# Input_v1_0.net
KiCad netlist of a schematic drawn in EAGLE
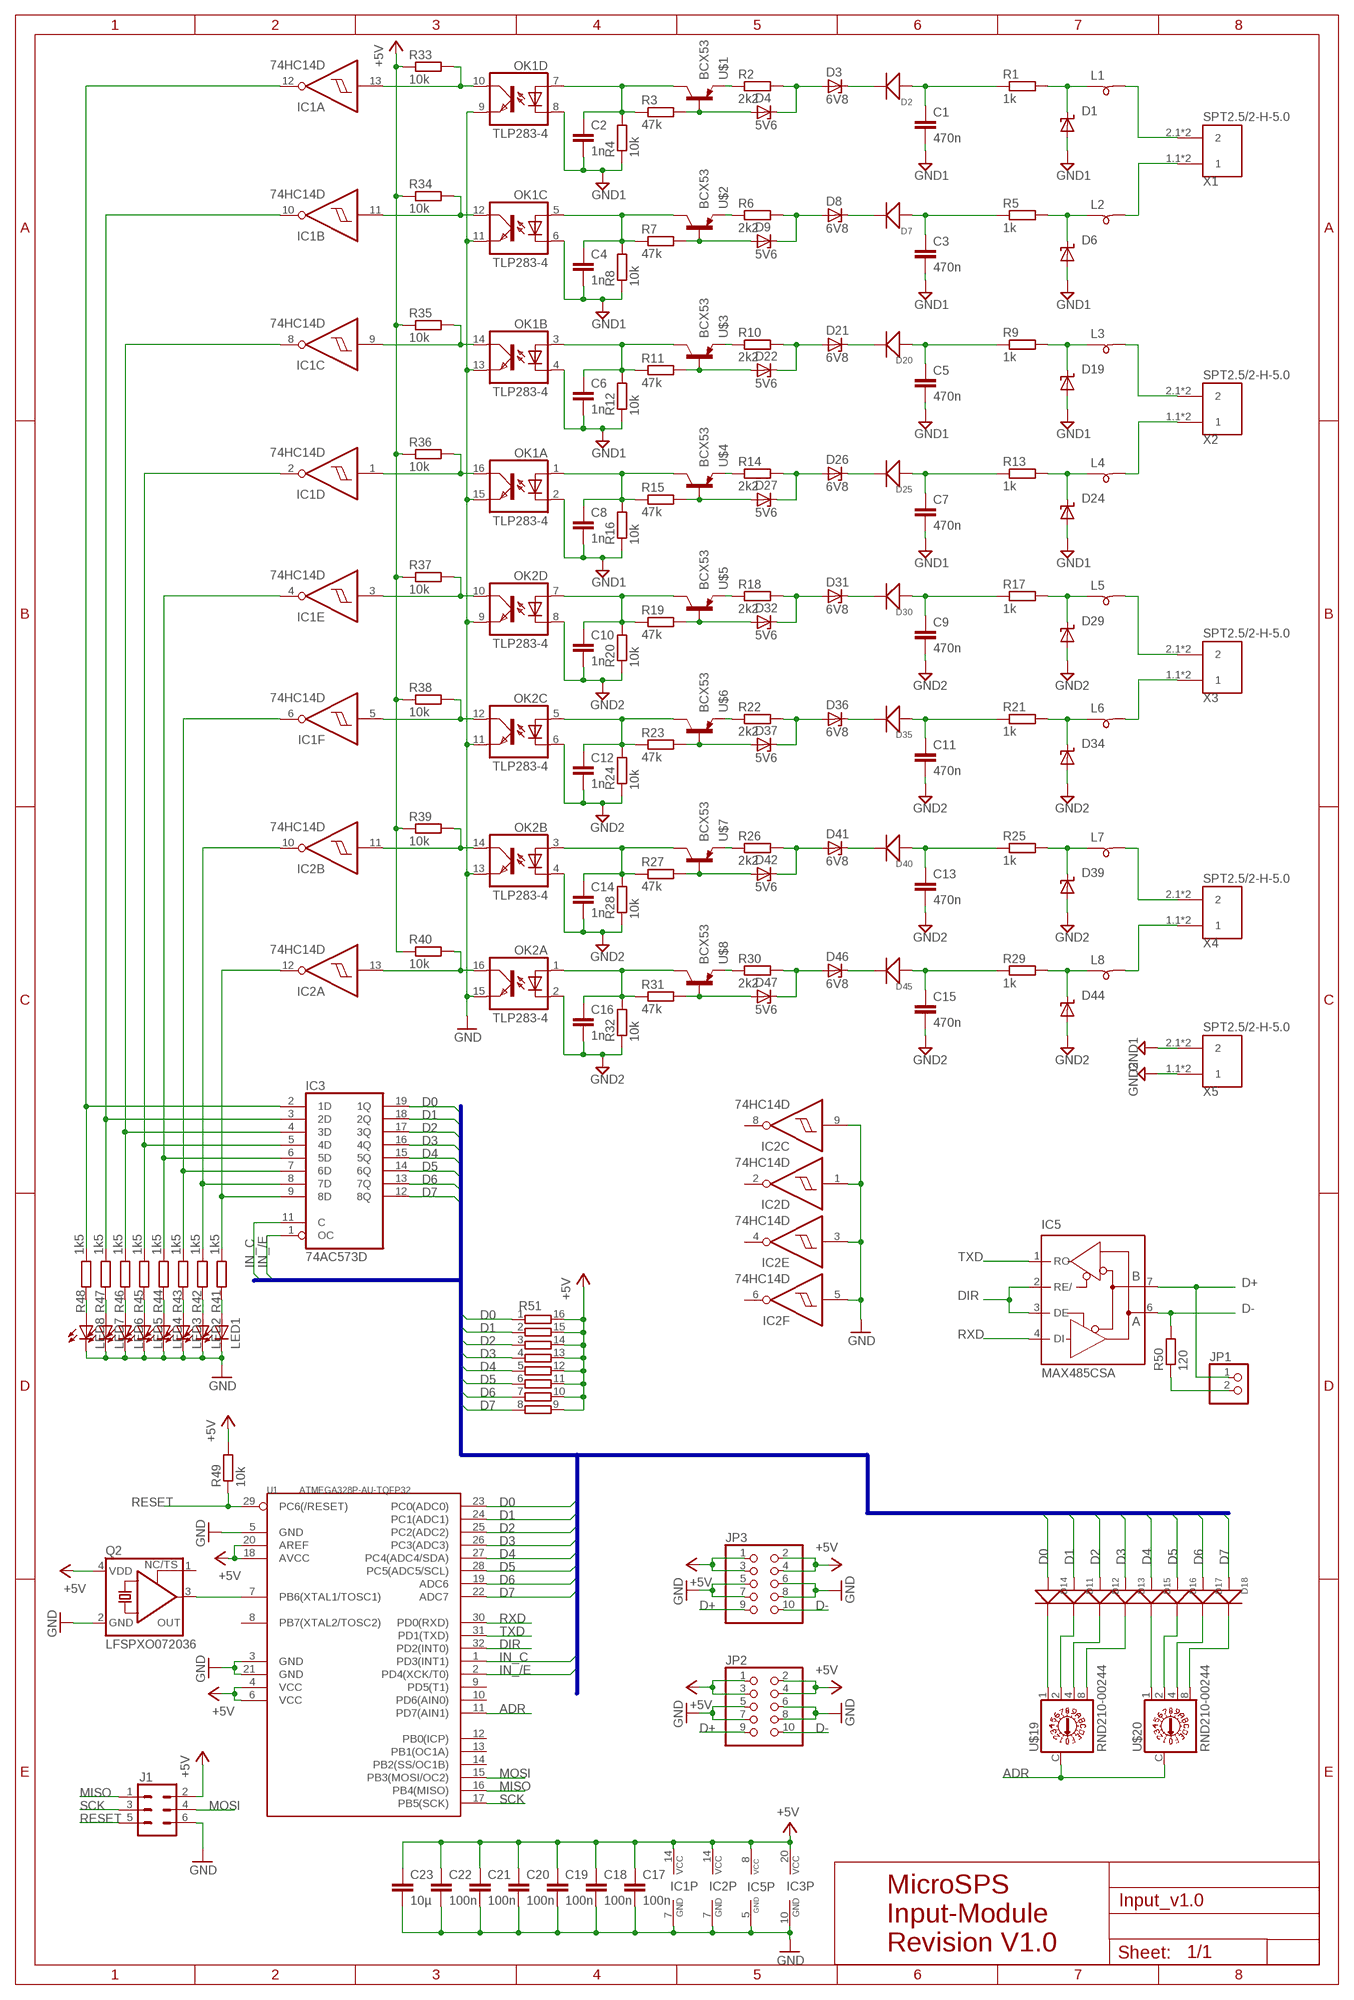
[diagram p0: schematic, sheet 1]

(export (version "E")
  (design (tool "Eeschema 10.0.6"))
  (components
    (comp (ref "C1")
      (value "470n")
      (footprint "eagle-import:C0805")
      (libsource (lib "eagle-import") (part "C-EUC0805"))
    )
    (comp (ref "C2")
      (value "1n")
      (footprint "eagle-import:C0805")
      (libsource (lib "eagle-import") (part "C-EUC0805"))
    )
    (comp (ref "C3")
      (value "470n")
      (footprint "eagle-import:C0805")
      (libsource (lib "eagle-import") (part "C-EUC0805"))
    )
    (comp (ref "C4")
      (value "1n")
      (footprint "eagle-import:C0805")
      (libsource (lib "eagle-import") (part "C-EUC0805"))
    )
    (comp (ref "C5")
      (value "470n")
      (footprint "eagle-import:C0805")
      (libsource (lib "eagle-import") (part "C-EUC0805"))
    )
    (comp (ref "C6")
      (value "1n")
      (footprint "eagle-import:C0805")
      (libsource (lib "eagle-import") (part "C-EUC0805"))
    )
    (comp (ref "C7")
      (value "470n")
      (footprint "eagle-import:C0805")
      (libsource (lib "eagle-import") (part "C-EUC0805"))
    )
    (comp (ref "C8")
      (value "1n")
      (footprint "eagle-import:C0805")
      (libsource (lib "eagle-import") (part "C-EUC0805"))
    )
    (comp (ref "C9")
      (value "470n")
      (footprint "eagle-import:C0805")
      (libsource (lib "eagle-import") (part "C-EUC0805"))
    )
    (comp (ref "C10")
      (value "1n")
      (footprint "eagle-import:C0805")
      (libsource (lib "eagle-import") (part "C-EUC0805"))
    )
    (comp (ref "C11")
      (value "470n")
      (footprint "eagle-import:C0805")
      (libsource (lib "eagle-import") (part "C-EUC0805"))
    )
    (comp (ref "C12")
      (value "1n")
      (footprint "eagle-import:C0805")
      (libsource (lib "eagle-import") (part "C-EUC0805"))
    )
    (comp (ref "C13")
      (value "470n")
      (footprint "eagle-import:C0805")
      (libsource (lib "eagle-import") (part "C-EUC0805"))
    )
    (comp (ref "C14")
      (value "1n")
      (footprint "eagle-import:C0805")
      (libsource (lib "eagle-import") (part "C-EUC0805"))
    )
    (comp (ref "C15")
      (value "470n")
      (footprint "eagle-import:C0805")
      (libsource (lib "eagle-import") (part "C-EUC0805"))
    )
    (comp (ref "C16")
      (value "1n")
      (footprint "eagle-import:C0805")
      (libsource (lib "eagle-import") (part "C-EUC0805"))
    )
    (comp (ref "C17")
      (value "100n")
      (footprint "eagle-import:C0805")
      (libsource (lib "eagle-import") (part "C-EUC0805"))
    )
    (comp (ref "C18")
      (value "100n")
      (footprint "eagle-import:C0805")
      (libsource (lib "eagle-import") (part "C-EUC0805"))
    )
    (comp (ref "C19")
      (value "100n")
      (footprint "eagle-import:C0805")
      (libsource (lib "eagle-import") (part "C-EUC0805"))
    )
    (comp (ref "C20")
      (value "100n")
      (footprint "eagle-import:C0805")
      (libsource (lib "eagle-import") (part "C-EUC0805"))
    )
    (comp (ref "C21")
      (value "100n")
      (footprint "eagle-import:C0805")
      (libsource (lib "eagle-import") (part "C-EUC0805"))
    )
    (comp (ref "C22")
      (value "100n")
      (footprint "eagle-import:C0805")
      (libsource (lib "eagle-import") (part "C-EUC0805"))
    )
    (comp (ref "C23")
      (value "10µ")
      (footprint "eagle-import:C0805")
      (libsource (lib "eagle-import") (part "C-EUC0805"))
    )
    (comp (ref "D1")
      (value "SUPPRESSOR-SMBJ")
      (footprint "eagle-import:SMBJ")
      (libsource (lib "eagle-import") (part "SUPPRESSOR-SMBJ"))
    )
    (comp (ref "D2")
      (value "DIODE'1N4148-SMD'")
      (footprint "eagle-import:LL-34")
      (libsource (lib "eagle-import") (part "DIODE'1N4148-SMD'"))
    )
    (comp (ref "D3")
      (value "6V8")
      (footprint "eagle-import:SOD80C")
      (libsource (lib "eagle-import") (part "ZENER-DIODESOD80C"))
    )
    (comp (ref "D4")
      (value "5V6")
      (footprint "eagle-import:SOD80C")
      (libsource (lib "eagle-import") (part "ZENER-DIODESOD80C"))
    )
    (comp (ref "D6")
      (value "SUPPRESSOR-SMBJ")
      (footprint "eagle-import:SMBJ")
      (libsource (lib "eagle-import") (part "SUPPRESSOR-SMBJ"))
    )
    (comp (ref "D7")
      (value "DIODE'1N4148-SMD'")
      (footprint "eagle-import:LL-34")
      (libsource (lib "eagle-import") (part "DIODE'1N4148-SMD'"))
    )
    (comp (ref "D8")
      (value "6V8")
      (footprint "eagle-import:SOD80C")
      (libsource (lib "eagle-import") (part "ZENER-DIODESOD80C"))
    )
    (comp (ref "D9")
      (value "5V6")
      (footprint "eagle-import:SOD80C")
      (libsource (lib "eagle-import") (part "ZENER-DIODESOD80C"))
    )
    (comp (ref "D11")
      (value "DIODE'1N4148-SMD'")
      (footprint "eagle-import:LL-34")
      (libsource (lib "eagle-import") (part "DIODE'1N4148-SMD'"))
    )
    (comp (ref "D12")
      (value "DIODE'1N4148-SMD'")
      (footprint "eagle-import:LL-34")
      (libsource (lib "eagle-import") (part "DIODE'1N4148-SMD'"))
    )
    (comp (ref "D13")
      (value "DIODE'1N4148-SMD'")
      (footprint "eagle-import:LL-34")
      (libsource (lib "eagle-import") (part "DIODE'1N4148-SMD'"))
    )
    (comp (ref "D14")
      (value "DIODE'1N4148-SMD'")
      (footprint "eagle-import:LL-34")
      (libsource (lib "eagle-import") (part "DIODE'1N4148-SMD'"))
    )
    (comp (ref "D15")
      (value "DIODE'1N4148-SMD'")
      (footprint "eagle-import:LL-34")
      (libsource (lib "eagle-import") (part "DIODE'1N4148-SMD'"))
    )
    (comp (ref "D16")
      (value "DIODE'1N4148-SMD'")
      (footprint "eagle-import:LL-34")
      (libsource (lib "eagle-import") (part "DIODE'1N4148-SMD'"))
    )
    (comp (ref "D17")
      (value "DIODE'1N4148-SMD'")
      (footprint "eagle-import:LL-34")
      (libsource (lib "eagle-import") (part "DIODE'1N4148-SMD'"))
    )
    (comp (ref "D18")
      (value "DIODE'1N4148-SMD'")
      (footprint "eagle-import:LL-34")
      (libsource (lib "eagle-import") (part "DIODE'1N4148-SMD'"))
    )
    (comp (ref "D19")
      (value "SUPPRESSOR-SMBJ")
      (footprint "eagle-import:SMBJ")
      (libsource (lib "eagle-import") (part "SUPPRESSOR-SMBJ"))
    )
    (comp (ref "D20")
      (value "DIODE'1N4148-SMD'")
      (footprint "eagle-import:LL-34")
      (libsource (lib "eagle-import") (part "DIODE'1N4148-SMD'"))
    )
    (comp (ref "D21")
      (value "6V8")
      (footprint "eagle-import:SOD80C")
      (libsource (lib "eagle-import") (part "ZENER-DIODESOD80C"))
    )
    (comp (ref "D22")
      (value "5V6")
      (footprint "eagle-import:SOD80C")
      (libsource (lib "eagle-import") (part "ZENER-DIODESOD80C"))
    )
    (comp (ref "D24")
      (value "SUPPRESSOR-SMBJ")
      (footprint "eagle-import:SMBJ")
      (libsource (lib "eagle-import") (part "SUPPRESSOR-SMBJ"))
    )
    (comp (ref "D25")
      (value "DIODE'1N4148-SMD'")
      (footprint "eagle-import:LL-34")
      (libsource (lib "eagle-import") (part "DIODE'1N4148-SMD'"))
    )
    (comp (ref "D26")
      (value "6V8")
      (footprint "eagle-import:SOD80C")
      (libsource (lib "eagle-import") (part "ZENER-DIODESOD80C"))
    )
    (comp (ref "D27")
      (value "5V6")
      (footprint "eagle-import:SOD80C")
      (libsource (lib "eagle-import") (part "ZENER-DIODESOD80C"))
    )
    (comp (ref "D29")
      (value "SUPPRESSOR-SMBJ")
      (footprint "eagle-import:SMBJ")
      (libsource (lib "eagle-import") (part "SUPPRESSOR-SMBJ"))
    )
    (comp (ref "D30")
      (value "DIODE'1N4148-SMD'")
      (footprint "eagle-import:LL-34")
      (libsource (lib "eagle-import") (part "DIODE'1N4148-SMD'"))
    )
    (comp (ref "D31")
      (value "6V8")
      (footprint "eagle-import:SOD80C")
      (libsource (lib "eagle-import") (part "ZENER-DIODESOD80C"))
    )
    (comp (ref "D32")
      (value "5V6")
      (footprint "eagle-import:SOD80C")
      (libsource (lib "eagle-import") (part "ZENER-DIODESOD80C"))
    )
    (comp (ref "D34")
      (value "SUPPRESSOR-SMBJ")
      (footprint "eagle-import:SMBJ")
      (libsource (lib "eagle-import") (part "SUPPRESSOR-SMBJ"))
    )
    (comp (ref "D35")
      (value "DIODE'1N4148-SMD'")
      (footprint "eagle-import:LL-34")
      (libsource (lib "eagle-import") (part "DIODE'1N4148-SMD'"))
    )
    (comp (ref "D36")
      (value "6V8")
      (footprint "eagle-import:SOD80C")
      (libsource (lib "eagle-import") (part "ZENER-DIODESOD80C"))
    )
    (comp (ref "D37")
      (value "5V6")
      (footprint "eagle-import:SOD80C")
      (libsource (lib "eagle-import") (part "ZENER-DIODESOD80C"))
    )
    (comp (ref "D39")
      (value "SUPPRESSOR-SMBJ")
      (footprint "eagle-import:SMBJ")
      (libsource (lib "eagle-import") (part "SUPPRESSOR-SMBJ"))
    )
    (comp (ref "D40")
      (value "DIODE'1N4148-SMD'")
      (footprint "eagle-import:LL-34")
      (libsource (lib "eagle-import") (part "DIODE'1N4148-SMD'"))
    )
    (comp (ref "D41")
      (value "6V8")
      (footprint "eagle-import:SOD80C")
      (libsource (lib "eagle-import") (part "ZENER-DIODESOD80C"))
    )
    (comp (ref "D42")
      (value "5V6")
      (footprint "eagle-import:SOD80C")
      (libsource (lib "eagle-import") (part "ZENER-DIODESOD80C"))
    )
    (comp (ref "D44")
      (value "SUPPRESSOR-SMBJ")
      (footprint "eagle-import:SMBJ")
      (libsource (lib "eagle-import") (part "SUPPRESSOR-SMBJ"))
    )
    (comp (ref "D45")
      (value "DIODE'1N4148-SMD'")
      (footprint "eagle-import:LL-34")
      (libsource (lib "eagle-import") (part "DIODE'1N4148-SMD'"))
    )
    (comp (ref "D46")
      (value "6V8")
      (footprint "eagle-import:SOD80C")
      (libsource (lib "eagle-import") (part "ZENER-DIODESOD80C"))
    )
    (comp (ref "D47")
      (value "5V6")
      (footprint "eagle-import:SOD80C")
      (libsource (lib "eagle-import") (part "ZENER-DIODESOD80C"))
    )
    (comp (ref "IC1")
      (value "74HC14D")
      (footprint "eagle-import:SO14")
      (libsource (lib "eagle-import") (part "7414DHC"))
    )
    (comp (ref "IC2")
      (value "74HC14D")
      (footprint "eagle-import:SO14")
      (libsource (lib "eagle-import") (part "7414DHC"))
    )
    (comp (ref "IC3")
      (value "74AC573D")
      (footprint "eagle-import:SO20W")
      (libsource (lib "eagle-import") (part "74573DAC"))
    )
    (comp (ref "IC5")
      (value "MAX485CSA")
      (footprint "eagle-import:SO08")
      (fields (field (name "MF") "MAXIM") (field (name "MPN") "MAX481CSA"))
      (libsource (lib "eagle-import") (part "MAX481CSA"))
    )
    (comp (ref "J1")
      (value "CONN_03X2FEMALE_SMD")
      (footprint "eagle-import:2X3_SMD")
      (libsource (lib "eagle-import") (part "CONN_03X2FEMALE_SMD"))
    )
    (comp (ref "JP1")
      (value "PINHD-1X2")
      (footprint "eagle-import:1X02")
      (libsource (lib "eagle-import") (part "PINHD-1X2"))
    )
    (comp (ref "JP2")
      (value "PINHD-2X5/90")
      (footprint "eagle-import:2X05_90")
      (libsource (lib "eagle-import") (part "PINHD-2X5/90"))
    )
    (comp (ref "JP3")
      (value "PINHD-2X5/90")
      (footprint "eagle-import:2X05_90")
      (libsource (lib "eagle-import") (part "PINHD-2X5/90"))
    )
    (comp (ref "L1")
      (value "SM-B5")
      (footprint "eagle-import:SM-B5")
      (libsource (lib "eagle-import") (part "SM-B5"))
    )
    (comp (ref "L2")
      (value "SM-B5")
      (footprint "eagle-import:SM-B5")
      (libsource (lib "eagle-import") (part "SM-B5"))
    )
    (comp (ref "L3")
      (value "SM-B5")
      (footprint "eagle-import:SM-B5")
      (libsource (lib "eagle-import") (part "SM-B5"))
    )
    (comp (ref "L4")
      (value "SM-B5")
      (footprint "eagle-import:SM-B5")
      (libsource (lib "eagle-import") (part "SM-B5"))
    )
    (comp (ref "L5")
      (value "SM-B5")
      (footprint "eagle-import:SM-B5")
      (libsource (lib "eagle-import") (part "SM-B5"))
    )
    (comp (ref "L6")
      (value "SM-B5")
      (footprint "eagle-import:SM-B5")
      (libsource (lib "eagle-import") (part "SM-B5"))
    )
    (comp (ref "L7")
      (value "SM-B5")
      (footprint "eagle-import:SM-B5")
      (libsource (lib "eagle-import") (part "SM-B5"))
    )
    (comp (ref "L8")
      (value "SM-B5")
      (footprint "eagle-import:SM-B5")
      (libsource (lib "eagle-import") (part "SM-B5"))
    )
    (comp (ref "LED1")
      (value "LED3MM")
      (footprint "eagle-import:LED3MM")
      (libsource (lib "eagle-import") (part "LED3MM"))
    )
    (comp (ref "LED2")
      (value "LED3MM")
      (footprint "eagle-import:LED3MM")
      (libsource (lib "eagle-import") (part "LED3MM"))
    )
    (comp (ref "LED3")
      (value "LED3MM")
      (footprint "eagle-import:LED3MM")
      (libsource (lib "eagle-import") (part "LED3MM"))
    )
    (comp (ref "LED4")
      (value "LED3MM")
      (footprint "eagle-import:LED3MM")
      (libsource (lib "eagle-import") (part "LED3MM"))
    )
    (comp (ref "LED5")
      (value "LED3MM")
      (footprint "eagle-import:LED3MM")
      (libsource (lib "eagle-import") (part "LED3MM"))
    )
    (comp (ref "LED6")
      (value "LED3MM")
      (footprint "eagle-import:LED3MM")
      (libsource (lib "eagle-import") (part "LED3MM"))
    )
    (comp (ref "LED7")
      (value "LED3MM")
      (footprint "eagle-import:LED3MM")
      (libsource (lib "eagle-import") (part "LED3MM"))
    )
    (comp (ref "LED8")
      (value "LED3MM")
      (footprint "eagle-import:LED3MM")
      (libsource (lib "eagle-import") (part "LED3MM"))
    )
    (comp (ref "OK1")
      (value "TLP283-4")
      (footprint "eagle-import:MINI-FLAT-16")
      (libsource (lib "eagle-import") (part "TLP283-4"))
    )
    (comp (ref "OK2")
      (value "TLP283-4")
      (footprint "eagle-import:MINI-FLAT-16")
      (libsource (lib "eagle-import") (part "TLP283-4"))
    )
    (comp (ref "Q2")
      (value "LFSPXO072036")
      (footprint "eagle-import:5.0X3.2_KXO-56")
      (libsource (lib "eagle-import") (part "KXO-PXO/XO-56-56"))
    )
    (comp (ref "R1")
      (value "1k")
      (footprint "eagle-import:R0805")
      (libsource (lib "eagle-import") (part "R-EU_R0805"))
    )
    (comp (ref "R2")
      (value "2k2")
      (footprint "eagle-import:R0805")
      (libsource (lib "eagle-import") (part "R-EU_R0805"))
    )
    (comp (ref "R3")
      (value "47k")
      (footprint "eagle-import:R0805")
      (libsource (lib "eagle-import") (part "R-EU_R0805"))
    )
    (comp (ref "R4")
      (value "10k")
      (footprint "eagle-import:R0805")
      (libsource (lib "eagle-import") (part "R-EU_R0805"))
    )
    (comp (ref "R5")
      (value "1k")
      (footprint "eagle-import:R0805")
      (libsource (lib "eagle-import") (part "R-EU_R0805"))
    )
    (comp (ref "R6")
      (value "2k2")
      (footprint "eagle-import:R0805")
      (libsource (lib "eagle-import") (part "R-EU_R0805"))
    )
    (comp (ref "R7")
      (value "47k")
      (footprint "eagle-import:R0805")
      (libsource (lib "eagle-import") (part "R-EU_R0805"))
    )
    (comp (ref "R8")
      (value "10k")
      (footprint "eagle-import:R0805")
      (libsource (lib "eagle-import") (part "R-EU_R0805"))
    )
    (comp (ref "R9")
      (value "1k")
      (footprint "eagle-import:R0805")
      (libsource (lib "eagle-import") (part "R-EU_R0805"))
    )
    (comp (ref "R10")
      (value "2k2")
      (footprint "eagle-import:R0805")
      (libsource (lib "eagle-import") (part "R-EU_R0805"))
    )
    (comp (ref "R11")
      (value "47k")
      (footprint "eagle-import:R0805")
      (libsource (lib "eagle-import") (part "R-EU_R0805"))
    )
    (comp (ref "R12")
      (value "10k")
      (footprint "eagle-import:R0805")
      (libsource (lib "eagle-import") (part "R-EU_R0805"))
    )
    (comp (ref "R13")
      (value "1k")
      (footprint "eagle-import:R0805")
      (libsource (lib "eagle-import") (part "R-EU_R0805"))
    )
    (comp (ref "R14")
      (value "2k2")
      (footprint "eagle-import:R0805")
      (libsource (lib "eagle-import") (part "R-EU_R0805"))
    )
    (comp (ref "R15")
      (value "47k")
      (footprint "eagle-import:R0805")
      (libsource (lib "eagle-import") (part "R-EU_R0805"))
    )
    (comp (ref "R16")
      (value "10k")
      (footprint "eagle-import:R0805")
      (libsource (lib "eagle-import") (part "R-EU_R0805"))
    )
    (comp (ref "R17")
      (value "1k")
      (footprint "eagle-import:R0805")
      (libsource (lib "eagle-import") (part "R-EU_R0805"))
    )
    (comp (ref "R18")
      (value "2k2")
      (footprint "eagle-import:R0805")
      (libsource (lib "eagle-import") (part "R-EU_R0805"))
    )
    (comp (ref "R19")
      (value "47k")
      (footprint "eagle-import:R0805")
      (libsource (lib "eagle-import") (part "R-EU_R0805"))
    )
    (comp (ref "R20")
      (value "10k")
      (footprint "eagle-import:R0805")
      (libsource (lib "eagle-import") (part "R-EU_R0805"))
    )
    (comp (ref "R21")
      (value "1k")
      (footprint "eagle-import:R0805")
      (libsource (lib "eagle-import") (part "R-EU_R0805"))
    )
    (comp (ref "R22")
      (value "2k2")
      (footprint "eagle-import:R0805")
      (libsource (lib "eagle-import") (part "R-EU_R0805"))
    )
    (comp (ref "R23")
      (value "47k")
      (footprint "eagle-import:R0805")
      (libsource (lib "eagle-import") (part "R-EU_R0805"))
    )
    (comp (ref "R24")
      (value "10k")
      (footprint "eagle-import:R0805")
      (libsource (lib "eagle-import") (part "R-EU_R0805"))
    )
    (comp (ref "R25")
      (value "1k")
      (footprint "eagle-import:R0805")
      (libsource (lib "eagle-import") (part "R-EU_R0805"))
    )
    (comp (ref "R26")
      (value "2k2")
      (footprint "eagle-import:R0805")
      (libsource (lib "eagle-import") (part "R-EU_R0805"))
    )
    (comp (ref "R27")
      (value "47k")
      (footprint "eagle-import:R0805")
      (libsource (lib "eagle-import") (part "R-EU_R0805"))
    )
    (comp (ref "R28")
      (value "10k")
      (footprint "eagle-import:R0805")
      (libsource (lib "eagle-import") (part "R-EU_R0805"))
    )
    (comp (ref "R29")
      (value "1k")
      (footprint "eagle-import:R0805")
      (libsource (lib "eagle-import") (part "R-EU_R0805"))
    )
    (comp (ref "R30")
      (value "2k2")
      (footprint "eagle-import:R0805")
      (libsource (lib "eagle-import") (part "R-EU_R0805"))
    )
    (comp (ref "R31")
      (value "47k")
      (footprint "eagle-import:R0805")
      (libsource (lib "eagle-import") (part "R-EU_R0805"))
    )
    (comp (ref "R32")
      (value "10k")
      (footprint "eagle-import:R0805")
      (libsource (lib "eagle-import") (part "R-EU_R0805"))
    )
    (comp (ref "R33")
      (value "10k")
      (footprint "eagle-import:R0805")
      (libsource (lib "eagle-import") (part "R-EU_R0805"))
    )
    (comp (ref "R34")
      (value "10k")
      (footprint "eagle-import:R0805")
      (libsource (lib "eagle-import") (part "R-EU_R0805"))
    )
    (comp (ref "R35")
      (value "10k")
      (footprint "eagle-import:R0805")
      (libsource (lib "eagle-import") (part "R-EU_R0805"))
    )
    (comp (ref "R36")
      (value "10k")
      (footprint "eagle-import:R0805")
      (libsource (lib "eagle-import") (part "R-EU_R0805"))
    )
    (comp (ref "R37")
      (value "10k")
      (footprint "eagle-import:R0805")
      (libsource (lib "eagle-import") (part "R-EU_R0805"))
    )
    (comp (ref "R38")
      (value "10k")
      (footprint "eagle-import:R0805")
      (libsource (lib "eagle-import") (part "R-EU_R0805"))
    )
    (comp (ref "R39")
      (value "10k")
      (footprint "eagle-import:R0805")
      (libsource (lib "eagle-import") (part "R-EU_R0805"))
    )
    (comp (ref "R40")
      (value "10k")
      (footprint "eagle-import:R0805")
      (libsource (lib "eagle-import") (part "R-EU_R0805"))
    )
    (comp (ref "R41")
      (value "1k5")
      (footprint "eagle-import:R0805")
      (libsource (lib "eagle-import") (part "R-EU_R0805"))
    )
    (comp (ref "R42")
      (value "1k5")
      (footprint "eagle-import:R0805")
      (libsource (lib "eagle-import") (part "R-EU_R0805"))
    )
    (comp (ref "R43")
      (value "1k5")
      (footprint "eagle-import:R0805")
      (libsource (lib "eagle-import") (part "R-EU_R0805"))
    )
    (comp (ref "R44")
      (value "1k5")
      (footprint "eagle-import:R0805")
      (libsource (lib "eagle-import") (part "R-EU_R0805"))
    )
    (comp (ref "R45")
      (value "1k5")
      (footprint "eagle-import:R0805")
      (libsource (lib "eagle-import") (part "R-EU_R0805"))
    )
    (comp (ref "R46")
      (value "1k5")
      (footprint "eagle-import:R0805")
      (libsource (lib "eagle-import") (part "R-EU_R0805"))
    )
    (comp (ref "R47")
      (value "1k5")
      (footprint "eagle-import:R0805")
      (libsource (lib "eagle-import") (part "R-EU_R0805"))
    )
    (comp (ref "R48")
      (value "1k5")
      (footprint "eagle-import:R0805")
      (libsource (lib "eagle-import") (part "R-EU_R0805"))
    )
    (comp (ref "R49")
      (value "10k")
      (footprint "eagle-import:R0805")
      (libsource (lib "eagle-import") (part "R-EU_R0805"))
    )
    (comp (ref "R50")
      (value "120")
      (footprint "eagle-import:R0805")
      (libsource (lib "eagle-import") (part "R-EU_R0805"))
    )
    (comp (ref "R51")
      (value "4816P-T01")
      (footprint "eagle-import:4816P")
      (fields (field (name "MF") "BOURNS, INC.") (field (name "MPN") "4816P-T01-684LF"))
      (libsource (lib "eagle-import") (part "4816P-T01"))
    )
    (comp (ref "U$1")
      (value "BCX53")
      (footprint "eagle-import:SOT89")
      (libsource (lib "eagle-import") (part "BCX53"))
    )
    (comp (ref "U$2")
      (value "BCX53")
      (footprint "eagle-import:SOT89")
      (libsource (lib "eagle-import") (part "BCX53"))
    )
    (comp (ref "U$3")
      (value "BCX53")
      (footprint "eagle-import:SOT89")
      (libsource (lib "eagle-import") (part "BCX53"))
    )
    (comp (ref "U$4")
      (value "BCX53")
      (footprint "eagle-import:SOT89")
      (libsource (lib "eagle-import") (part "BCX53"))
    )
    (comp (ref "U$5")
      (value "BCX53")
      (footprint "eagle-import:SOT89")
      (libsource (lib "eagle-import") (part "BCX53"))
    )
    (comp (ref "U$6")
      (value "BCX53")
      (footprint "eagle-import:SOT89")
      (libsource (lib "eagle-import") (part "BCX53"))
    )
    (comp (ref "U$7")
      (value "BCX53")
      (footprint "eagle-import:SOT89")
      (libsource (lib "eagle-import") (part "BCX53"))
    )
    (comp (ref "U$8")
      (value "BCX53")
      (footprint "eagle-import:SOT89")
      (libsource (lib "eagle-import") (part "BCX53"))
    )
    (comp (ref "U$19")
      (value "RND210-00244")
      (footprint "eagle-import:RND210-00244")
      (libsource (lib "eagle-import") (part "RND210-00244"))
    )
    (comp (ref "U$20")
      (value "RND210-00244")
      (footprint "eagle-import:RND210-00244")
      (libsource (lib "eagle-import") (part "RND210-00244"))
    )
    (comp (ref "U1")
      (value "ATMEGA328P-AU-TQFP32")
      (footprint "eagle-import:TQFP32-0.8-7X7MM")
      (fields (field (name "MPN") "ATMEGA328P-AU"))
      (libsource (lib "eagle-import") (part "MCU-ATMEGA328P-AU(TQFP32)"))
    )
    (comp (ref "X1")
      (value "SPT2.5/2-H-5.0")
      (footprint "eagle-import:SPT2")
      (libsource (lib "eagle-import") (part "SPT2.5/2-H-5.0"))
    )
    (comp (ref "X2")
      (value "SPT2.5/2-H-5.0")
      (footprint "eagle-import:SPT2")
      (libsource (lib "eagle-import") (part "SPT2.5/2-H-5.0"))
    )
    (comp (ref "X3")
      (value "SPT2.5/2-H-5.0")
      (footprint "eagle-import:SPT2")
      (libsource (lib "eagle-import") (part "SPT2.5/2-H-5.0"))
    )
    (comp (ref "X4")
      (value "SPT2.5/2-H-5.0")
      (footprint "eagle-import:SPT2")
      (libsource (lib "eagle-import") (part "SPT2.5/2-H-5.0"))
    )
    (comp (ref "X5")
      (value "SPT2.5/2-H-5.0")
      (footprint "eagle-import:SPT2")
      (libsource (lib "eagle-import") (part "SPT2.5/2-H-5.0"))
    )
  )
  (nets
    (net (code "1") (name "+5V") (class "Default")
      (node (ref "C17") (pin "1") (pinfunction "1_1") (pintype "passive"))
      (node (ref "C18") (pin "1") (pinfunction "1_1") (pintype "passive"))
      (node (ref "C19") (pin "1") (pinfunction "1_1") (pintype "passive"))
      (node (ref "C20") (pin "1") (pinfunction "1_1") (pintype "passive"))
      (node (ref "C21") (pin "1") (pinfunction "1_1") (pintype "passive"))
      (node (ref "C22") (pin "1") (pinfunction "1_1") (pintype "passive"))
      (node (ref "C23") (pin "1") (pinfunction "1_1") (pintype "passive"))
      (node (ref "IC1") (pin "14") (pinfunction "VCC_14") (pintype "power_in"))
      (node (ref "IC2") (pin "14") (pinfunction "VCC_14") (pintype "power_in"))
      (node (ref "IC3") (pin "20") (pinfunction "VCC_20") (pintype "power_in"))
      (node (ref "IC5") (pin "8") (pinfunction "VCC_8") (pintype "power_in"))
      (node (ref "J1") (pin "2") (pinfunction "2_2") (pintype "bidirectional"))
      (node (ref "JP2") (pin "1") (pinfunction "1_1") (pintype "passive"))
      (node (ref "JP2") (pin "2") (pinfunction "2_2") (pintype "passive"))
      (node (ref "JP2") (pin "3") (pinfunction "3_3") (pintype "passive"))
      (node (ref "JP2") (pin "4") (pinfunction "4_4") (pintype "passive"))
      (node (ref "JP3") (pin "1") (pinfunction "1_1") (pintype "passive"))
      (node (ref "JP3") (pin "2") (pinfunction "2_2") (pintype "passive"))
      (node (ref "JP3") (pin "3") (pinfunction "3_3") (pintype "passive"))
      (node (ref "JP3") (pin "4") (pinfunction "4_4") (pintype "passive"))
      (node (ref "Q2") (pin "4") (pinfunction "VDD_4") (pintype "power_in"))
      (node (ref "R33") (pin "1") (pinfunction "1_1") (pintype "passive"))
      (node (ref "R34") (pin "1") (pinfunction "1_1") (pintype "passive"))
      (node (ref "R35") (pin "1") (pinfunction "1_1") (pintype "passive"))
      (node (ref "R36") (pin "1") (pinfunction "1_1") (pintype "passive"))
      (node (ref "R37") (pin "1") (pinfunction "1_1") (pintype "passive"))
      (node (ref "R38") (pin "1") (pinfunction "1_1") (pintype "passive"))
      (node (ref "R39") (pin "1") (pinfunction "1_1") (pintype "passive"))
      (node (ref "R40") (pin "1") (pinfunction "1_1") (pintype "passive"))
      (node (ref "R49") (pin "2") (pinfunction "2_2") (pintype "passive"))
      (node (ref "R51") (pin "10") (pinfunction "10_10") (pintype "passive"))
      (node (ref "R51") (pin "11") (pinfunction "11_11") (pintype "passive"))
      (node (ref "R51") (pin "12") (pinfunction "12_12") (pintype "passive"))
      (node (ref "R51") (pin "13") (pinfunction "13_13") (pintype "passive"))
      (node (ref "R51") (pin "14") (pinfunction "14_14") (pintype "passive"))
      (node (ref "R51") (pin "15") (pinfunction "15_15") (pintype "passive"))
      (node (ref "R51") (pin "16") (pinfunction "16_16") (pintype "passive"))
      (node (ref "R51") (pin "9") (pinfunction "9_9") (pintype "passive"))
      (node (ref "U1") (pin "18") (pinfunction "AVCC_18") (pintype "bidirectional"))
      (node (ref "U1") (pin "20") (pinfunction "AREF_20") (pintype "bidirectional"))
      (node (ref "U1") (pin "4") (pinfunction "VCC_4") (pintype "bidirectional"))
      (node (ref "U1") (pin "6") (pinfunction "VCC_6") (pintype "bidirectional"))
    )
    (net (code "2") (name "/ADR") (class "Default")
      (node (ref "U$19") (pin "C") (pinfunction "C_C") (pintype "passive"))
      (node (ref "U$20") (pin "C") (pinfunction "C_C") (pintype "passive"))
      (node (ref "U1") (pin "11") (pinfunction "PD7(AIN1)_11") (pintype "bidirectional"))
    )
    (net (code "3") (name "/D+") (class "Default")
      (node (ref "IC5") (pin "7") (pinfunction "B_7") (pintype "passive"))
      (node (ref "JP1") (pin "1") (pinfunction "1_1") (pintype "passive"))
      (node (ref "JP2") (pin "9") (pinfunction "9_9") (pintype "passive"))
      (node (ref "JP3") (pin "9") (pinfunction "9_9") (pintype "passive"))
    )
    (net (code "4") (name "/D-") (class "Default")
      (node (ref "IC5") (pin "6") (pinfunction "A_6") (pintype "passive"))
      (node (ref "JP2") (pin "10") (pinfunction "10_10") (pintype "passive"))
      (node (ref "JP3") (pin "10") (pinfunction "10_10") (pintype "passive"))
      (node (ref "R50") (pin "2") (pinfunction "2_2") (pintype "passive"))
    )
    (net (code "5") (name "/D0") (class "Default")
      (node (ref "D14") (pin "A") (pinfunction "+_A") (pintype "passive"))
      (node (ref "IC3") (pin "19") (pinfunction "1Q_19") (pintype "tri_state"))
      (node (ref "R51") (pin "1") (pinfunction "1_1") (pintype "passive"))
      (node (ref "U1") (pin "23") (pinfunction "PC0(ADC0)_23") (pintype "bidirectional"))
    )
    (net (code "6") (name "/D1") (class "Default")
      (node (ref "D11") (pin "A") (pinfunction "+_A") (pintype "passive"))
      (node (ref "IC3") (pin "18") (pinfunction "2Q_18") (pintype "tri_state"))
      (node (ref "R51") (pin "2") (pinfunction "2_2") (pintype "passive"))
      (node (ref "U1") (pin "24") (pinfunction "PC1(ADC1)_24") (pintype "bidirectional"))
    )
    (net (code "7") (name "/D2") (class "Default")
      (node (ref "D12") (pin "A") (pinfunction "+_A") (pintype "passive"))
      (node (ref "IC3") (pin "17") (pinfunction "3Q_17") (pintype "tri_state"))
      (node (ref "R51") (pin "3") (pinfunction "3_3") (pintype "passive"))
      (node (ref "U1") (pin "25") (pinfunction "PC2(ADC2)_25") (pintype "bidirectional"))
    )
    (net (code "8") (name "/D3") (class "Default")
      (node (ref "D13") (pin "A") (pinfunction "+_A") (pintype "passive"))
      (node (ref "IC3") (pin "16") (pinfunction "4Q_16") (pintype "tri_state"))
      (node (ref "R51") (pin "4") (pinfunction "4_4") (pintype "passive"))
      (node (ref "U1") (pin "26") (pinfunction "PC3(ADC3)_26") (pintype "bidirectional"))
    )
    (net (code "9") (name "/D4") (class "Default")
      (node (ref "D15") (pin "A") (pinfunction "+_A") (pintype "passive"))
      (node (ref "IC3") (pin "15") (pinfunction "5Q_15") (pintype "tri_state"))
      (node (ref "R51") (pin "5") (pinfunction "5_5") (pintype "passive"))
      (node (ref "U1") (pin "27") (pinfunction "PC4(ADC4/SDA)_27") (pintype "bidirectional"))
    )
    (net (code "10") (name "/D5") (class "Default")
      (node (ref "D16") (pin "A") (pinfunction "+_A") (pintype "passive"))
      (node (ref "IC3") (pin "14") (pinfunction "6Q_14") (pintype "tri_state"))
      (node (ref "R51") (pin "6") (pinfunction "6_6") (pintype "passive"))
      (node (ref "U1") (pin "28") (pinfunction "PC5(ADC5/SCL)_28") (pintype "bidirectional"))
    )
    (net (code "11") (name "/D6") (class "Default")
      (node (ref "D17") (pin "A") (pinfunction "+_A") (pintype "passive"))
      (node (ref "IC3") (pin "13") (pinfunction "7Q_13") (pintype "tri_state"))
      (node (ref "R51") (pin "7") (pinfunction "7_7") (pintype "passive"))
      (node (ref "U1") (pin "19") (pinfunction "ADC6_19") (pintype "bidirectional"))
    )
    (net (code "12") (name "/D7") (class "Default")
      (node (ref "D18") (pin "A") (pinfunction "+_A") (pintype "passive"))
      (node (ref "IC3") (pin "12") (pinfunction "8Q_12") (pintype "tri_state"))
      (node (ref "R51") (pin "8") (pinfunction "8_8") (pintype "passive"))
      (node (ref "U1") (pin "22") (pinfunction "ADC7_22") (pintype "bidirectional"))
    )
    (net (code "13") (name "/DIR") (class "Default")
      (node (ref "IC5") (pin "2") (pinfunction "RE/_2") (pintype "input"))
      (node (ref "IC5") (pin "3") (pinfunction "DE_3") (pintype "input"))
      (node (ref "U1") (pin "32") (pinfunction "PD2(INT0)_32") (pintype "bidirectional"))
    )
    (net (code "14") (name "/IN_C") (class "Default")
      (node (ref "IC3") (pin "11") (pinfunction "C_11") (pintype "input"))
      (node (ref "U1") (pin "1") (pinfunction "PD3(INT1)_1") (pintype "bidirectional"))
    )
    (net (code "15") (name "/IN_{slash}E") (class "Default")
      (node (ref "IC3") (pin "1") (pinfunction "OC_1") (pintype "input"))
      (node (ref "U1") (pin "2") (pinfunction "PD4(XCK/T0)_2") (pintype "bidirectional"))
    )
    (net (code "16") (name "/MISO") (class "Default")
      (node (ref "J1") (pin "1") (pinfunction "1_1") (pintype "bidirectional"))
      (node (ref "U1") (pin "16") (pinfunction "PB4(MISO)_16") (pintype "bidirectional"))
    )
    (net (code "17") (name "/MOSI") (class "Default")
      (node (ref "J1") (pin "4") (pinfunction "4_4") (pintype "bidirectional"))
      (node (ref "U1") (pin "15") (pinfunction "PB3(MOSI/OC2)_15") (pintype "bidirectional"))
    )
    (net (code "18") (name "/RESET") (class "Default")
      (node (ref "J1") (pin "5") (pinfunction "5_5") (pintype "bidirectional"))
      (node (ref "R49") (pin "1") (pinfunction "1_1") (pintype "passive"))
      (node (ref "U1") (pin "29") (pinfunction "PC6(/RESET)_29") (pintype "bidirectional"))
    )
    (net (code "19") (name "/RXD") (class "Default")
      (node (ref "IC5") (pin "4") (pinfunction "DI_4") (pintype "input"))
      (node (ref "U1") (pin "30") (pinfunction "PD0(RXD)_30") (pintype "bidirectional"))
    )
    (net (code "20") (name "/SCK") (class "Default")
      (node (ref "J1") (pin "3") (pinfunction "3_3") (pintype "bidirectional"))
      (node (ref "U1") (pin "17") (pinfunction "PB5(SCK)_17") (pintype "bidirectional"))
    )
    (net (code "21") (name "/TXD") (class "Default")
      (node (ref "IC5") (pin "1") (pinfunction "RO_1") (pintype "output"))
      (node (ref "U1") (pin "31") (pinfunction "PD1(TXD)_31") (pintype "bidirectional"))
    )
    (net (code "22") (name "GND") (class "Default")
      (node (ref "C17") (pin "2") (pinfunction "2_2") (pintype "passive"))
      (node (ref "C18") (pin "2") (pinfunction "2_2") (pintype "passive"))
      (node (ref "C19") (pin "2") (pinfunction "2_2") (pintype "passive"))
      (node (ref "C20") (pin "2") (pinfunction "2_2") (pintype "passive"))
      (node (ref "C21") (pin "2") (pinfunction "2_2") (pintype "passive"))
      (node (ref "C22") (pin "2") (pinfunction "2_2") (pintype "passive"))
      (node (ref "C23") (pin "2") (pinfunction "2_2") (pintype "passive"))
      (node (ref "IC1") (pin "7") (pinfunction "GND_7") (pintype "power_in"))
      (node (ref "IC2") (pin "1") (pinfunction "I_1") (pintype "input"))
      (node (ref "IC2") (pin "3") (pinfunction "I_3") (pintype "input"))
      (node (ref "IC2") (pin "5") (pinfunction "I_5") (pintype "input"))
      (node (ref "IC2") (pin "7") (pinfunction "GND_7") (pintype "power_in"))
      (node (ref "IC2") (pin "9") (pinfunction "I_9") (pintype "input"))
      (node (ref "IC3") (pin "10") (pinfunction "GND_10") (pintype "power_in"))
      (node (ref "IC5") (pin "5") (pinfunction "GND_5") (pintype "power_in"))
      (node (ref "J1") (pin "6") (pinfunction "6_6") (pintype "bidirectional"))
      (node (ref "JP2") (pin "5") (pinfunction "5_5") (pintype "passive"))
      (node (ref "JP2") (pin "6") (pinfunction "6_6") (pintype "passive"))
      (node (ref "JP2") (pin "7") (pinfunction "7_7") (pintype "passive"))
      (node (ref "JP2") (pin "8") (pinfunction "8_8") (pintype "passive"))
      (node (ref "JP3") (pin "5") (pinfunction "5_5") (pintype "passive"))
      (node (ref "JP3") (pin "6") (pinfunction "6_6") (pintype "passive"))
      (node (ref "JP3") (pin "7") (pinfunction "7_7") (pintype "passive"))
      (node (ref "JP3") (pin "8") (pinfunction "8_8") (pintype "passive"))
      (node (ref "LED1") (pin "K") (pinfunction "C_K") (pintype "passive"))
      (node (ref "LED2") (pin "K") (pinfunction "C_K") (pintype "passive"))
      (node (ref "LED3") (pin "K") (pinfunction "C_K") (pintype "passive"))
      (node (ref "LED4") (pin "K") (pinfunction "C_K") (pintype "passive"))
      (node (ref "LED5") (pin "K") (pinfunction "C_K") (pintype "passive"))
      (node (ref "LED6") (pin "K") (pinfunction "C_K") (pintype "passive"))
      (node (ref "LED7") (pin "K") (pinfunction "C_K") (pintype "passive"))
      (node (ref "LED8") (pin "K") (pinfunction "C_K") (pintype "passive"))
      (node (ref "OK1") (pin "11") (pinfunction "EMIT_11") (pintype "passive"))
      (node (ref "OK1") (pin "13") (pinfunction "EMIT_13") (pintype "passive"))
      (node (ref "OK1") (pin "15") (pinfunction "EMIT_15") (pintype "passive"))
      (node (ref "OK1") (pin "9") (pinfunction "EMIT_9") (pintype "passive"))
      (node (ref "OK2") (pin "11") (pinfunction "EMIT_11") (pintype "passive"))
      (node (ref "OK2") (pin "13") (pinfunction "EMIT_13") (pintype "passive"))
      (node (ref "OK2") (pin "15") (pinfunction "EMIT_15") (pintype "passive"))
      (node (ref "OK2") (pin "9") (pinfunction "EMIT_9") (pintype "passive"))
      (node (ref "Q2") (pin "2") (pinfunction "GND_2") (pintype "power_in"))
      (node (ref "U1") (pin "21") (pinfunction "GND_21") (pintype "bidirectional"))
      (node (ref "U1") (pin "3") (pinfunction "GND_3") (pintype "bidirectional"))
      (node (ref "U1") (pin "5") (pinfunction "GND_5") (pintype "bidirectional"))
    )
    (net (code "23") (name "GND1") (class "Default")
      (node (ref "C1") (pin "2") (pinfunction "2_2") (pintype "passive"))
      (node (ref "C2") (pin "2") (pinfunction "2_2") (pintype "passive"))
      (node (ref "C3") (pin "2") (pinfunction "2_2") (pintype "passive"))
      (node (ref "C4") (pin "2") (pinfunction "2_2") (pintype "passive"))
      (node (ref "C5") (pin "2") (pinfunction "2_2") (pintype "passive"))
      (node (ref "C6") (pin "2") (pinfunction "2_2") (pintype "passive"))
      (node (ref "C7") (pin "2") (pinfunction "2_2") (pintype "passive"))
      (node (ref "C8") (pin "2") (pinfunction "2_2") (pintype "passive"))
      (node (ref "D1") (pin "A") (pinfunction "A_A") (pintype "passive"))
      (node (ref "D19") (pin "A") (pinfunction "A_A") (pintype "passive"))
      (node (ref "D24") (pin "A") (pinfunction "A_A") (pintype "passive"))
      (node (ref "D6") (pin "A") (pinfunction "A_A") (pintype "passive"))
      (node (ref "OK1") (pin "2") (pinfunction "C_2") (pintype "passive"))
      (node (ref "OK1") (pin "4") (pinfunction "C_4") (pintype "passive"))
      (node (ref "OK1") (pin "6") (pinfunction "C_6") (pintype "passive"))
      (node (ref "OK1") (pin "8") (pinfunction "C_8") (pintype "passive"))
      (node (ref "R12") (pin "1") (pinfunction "1_1") (pintype "passive"))
      (node (ref "R16") (pin "1") (pinfunction "1_1") (pintype "passive"))
      (node (ref "R4") (pin "1") (pinfunction "1_1") (pintype "passive"))
      (node (ref "R8") (pin "1") (pinfunction "1_1") (pintype "passive"))
      (node (ref "X5") (pin "2.1") (pinfunction "2_2.1") (pintype "bidirectional"))
      (node (ref "X5") (pin "2.2") (pinfunction "2_2.2") (pintype "bidirectional"))
    )
    (net (code "24") (name "GND2") (class "Default")
      (node (ref "C10") (pin "2") (pinfunction "2_2") (pintype "passive"))
      (node (ref "C11") (pin "2") (pinfunction "2_2") (pintype "passive"))
      (node (ref "C12") (pin "2") (pinfunction "2_2") (pintype "passive"))
      (node (ref "C13") (pin "2") (pinfunction "2_2") (pintype "passive"))
      (node (ref "C14") (pin "2") (pinfunction "2_2") (pintype "passive"))
      (node (ref "C15") (pin "2") (pinfunction "2_2") (pintype "passive"))
      (node (ref "C16") (pin "2") (pinfunction "2_2") (pintype "passive"))
      (node (ref "C9") (pin "2") (pinfunction "2_2") (pintype "passive"))
      (node (ref "D29") (pin "A") (pinfunction "A_A") (pintype "passive"))
      (node (ref "D34") (pin "A") (pinfunction "A_A") (pintype "passive"))
      (node (ref "D39") (pin "A") (pinfunction "A_A") (pintype "passive"))
      (node (ref "D44") (pin "A") (pinfunction "A_A") (pintype "passive"))
      (node (ref "OK2") (pin "2") (pinfunction "C_2") (pintype "passive"))
      (node (ref "OK2") (pin "4") (pinfunction "C_4") (pintype "passive"))
      (node (ref "OK2") (pin "6") (pinfunction "C_6") (pintype "passive"))
      (node (ref "OK2") (pin "8") (pinfunction "C_8") (pintype "passive"))
      (node (ref "R20") (pin "1") (pinfunction "1_1") (pintype "passive"))
      (node (ref "R24") (pin "1") (pinfunction "1_1") (pintype "passive"))
      (node (ref "R28") (pin "1") (pinfunction "1_1") (pintype "passive"))
      (node (ref "R32") (pin "1") (pinfunction "1_1") (pintype "passive"))
      (node (ref "X5") (pin "1.1") (pinfunction "1_1.1") (pintype "bidirectional"))
      (node (ref "X5") (pin "1.2") (pinfunction "1_1.2") (pintype "bidirectional"))
    )
    (net (code "25") (name "Net-(D1-PadC)") (class "Default")
      (node (ref "D1") (pin "C") (pinfunction "C_C") (pintype "passive"))
      (node (ref "L1") (pin "1") (pinfunction "1_1") (pintype "passive"))
      (node (ref "R1") (pin "2") (pinfunction "2_2") (pintype "passive"))
    )
    (net (code "26") (name "Net-(D2-+)") (class "Default")
      (node (ref "C1") (pin "1") (pinfunction "1_1") (pintype "passive"))
      (node (ref "D2") (pin "A") (pinfunction "+_A") (pintype "passive"))
      (node (ref "R1") (pin "1") (pinfunction "1_1") (pintype "passive"))
    )
    (net (code "27") (name "Net-(D2--)") (class "Default")
      (node (ref "D2") (pin "C") (pinfunction "-_C") (pintype "passive"))
      (node (ref "D3") (pin "C") (pinfunction "C_C") (pintype "passive"))
    )
    (net (code "28") (name "Net-(D3-PadA)") (class "Default")
      (node (ref "D3") (pin "A") (pinfunction "A_A") (pintype "passive"))
      (node (ref "D4") (pin "C") (pinfunction "C_C") (pintype "passive"))
      (node (ref "R2") (pin "2") (pinfunction "2_2") (pintype "passive"))
    )
    (net (code "29") (name "Net-(D6-PadC)") (class "Default")
      (node (ref "D6") (pin "C") (pinfunction "C_C") (pintype "passive"))
      (node (ref "L2") (pin "1") (pinfunction "1_1") (pintype "passive"))
      (node (ref "R5") (pin "2") (pinfunction "2_2") (pintype "passive"))
    )
    (net (code "30") (name "Net-(D7-+)") (class "Default")
      (node (ref "C3") (pin "1") (pinfunction "1_1") (pintype "passive"))
      (node (ref "D7") (pin "A") (pinfunction "+_A") (pintype "passive"))
      (node (ref "R5") (pin "1") (pinfunction "1_1") (pintype "passive"))
    )
    (net (code "31") (name "Net-(D7--)") (class "Default")
      (node (ref "D7") (pin "C") (pinfunction "-_C") (pintype "passive"))
      (node (ref "D8") (pin "C") (pinfunction "C_C") (pintype "passive"))
    )
    (net (code "32") (name "Net-(D8-PadA)") (class "Default")
      (node (ref "D8") (pin "A") (pinfunction "A_A") (pintype "passive"))
      (node (ref "D9") (pin "C") (pinfunction "C_C") (pintype "passive"))
      (node (ref "R6") (pin "2") (pinfunction "2_2") (pintype "passive"))
    )
    (net (code "33") (name "Net-(D11--)") (class "Default")
      (node (ref "D11") (pin "C") (pinfunction "-_C") (pintype "passive"))
      (node (ref "U$19") (pin "2") (pinfunction "2_2") (pintype "passive"))
    )
    (net (code "34") (name "Net-(D12--)") (class "Default")
      (node (ref "D12") (pin "C") (pinfunction "-_C") (pintype "passive"))
      (node (ref "U$19") (pin "4") (pinfunction "4_4") (pintype "passive"))
    )
    (net (code "35") (name "Net-(D13--)") (class "Default")
      (node (ref "D13") (pin "C") (pinfunction "-_C") (pintype "passive"))
      (node (ref "U$19") (pin "8") (pinfunction "8_8") (pintype "passive"))
    )
    (net (code "36") (name "Net-(D14--)") (class "Default")
      (node (ref "D14") (pin "C") (pinfunction "-_C") (pintype "passive"))
      (node (ref "U$19") (pin "1") (pinfunction "1_1") (pintype "passive"))
    )
    (net (code "37") (name "Net-(D15--)") (class "Default")
      (node (ref "D15") (pin "C") (pinfunction "-_C") (pintype "passive"))
      (node (ref "U$20") (pin "1") (pinfunction "1_1") (pintype "passive"))
    )
    (net (code "38") (name "Net-(D16--)") (class "Default")
      (node (ref "D16") (pin "C") (pinfunction "-_C") (pintype "passive"))
      (node (ref "U$20") (pin "2") (pinfunction "2_2") (pintype "passive"))
    )
    (net (code "39") (name "Net-(D17--)") (class "Default")
      (node (ref "D17") (pin "C") (pinfunction "-_C") (pintype "passive"))
      (node (ref "U$20") (pin "4") (pinfunction "4_4") (pintype "passive"))
    )
    (net (code "40") (name "Net-(D18--)") (class "Default")
      (node (ref "D18") (pin "C") (pinfunction "-_C") (pintype "passive"))
      (node (ref "U$20") (pin "8") (pinfunction "8_8") (pintype "passive"))
    )
    (net (code "41") (name "Net-(D19-PadC)") (class "Default")
      (node (ref "D19") (pin "C") (pinfunction "C_C") (pintype "passive"))
      (node (ref "L3") (pin "1") (pinfunction "1_1") (pintype "passive"))
      (node (ref "R9") (pin "2") (pinfunction "2_2") (pintype "passive"))
    )
    (net (code "42") (name "Net-(D20-+)") (class "Default")
      (node (ref "C5") (pin "1") (pinfunction "1_1") (pintype "passive"))
      (node (ref "D20") (pin "A") (pinfunction "+_A") (pintype "passive"))
      (node (ref "R9") (pin "1") (pinfunction "1_1") (pintype "passive"))
    )
    (net (code "43") (name "Net-(D20--)") (class "Default")
      (node (ref "D20") (pin "C") (pinfunction "-_C") (pintype "passive"))
      (node (ref "D21") (pin "C") (pinfunction "C_C") (pintype "passive"))
    )
    (net (code "44") (name "Net-(D21-PadA)") (class "Default")
      (node (ref "D21") (pin "A") (pinfunction "A_A") (pintype "passive"))
      (node (ref "D22") (pin "C") (pinfunction "C_C") (pintype "passive"))
      (node (ref "R10") (pin "2") (pinfunction "2_2") (pintype "passive"))
    )
    (net (code "45") (name "Net-(D24-PadC)") (class "Default")
      (node (ref "D24") (pin "C") (pinfunction "C_C") (pintype "passive"))
      (node (ref "L4") (pin "1") (pinfunction "1_1") (pintype "passive"))
      (node (ref "R13") (pin "2") (pinfunction "2_2") (pintype "passive"))
    )
    (net (code "46") (name "Net-(D25-+)") (class "Default")
      (node (ref "C7") (pin "1") (pinfunction "1_1") (pintype "passive"))
      (node (ref "D25") (pin "A") (pinfunction "+_A") (pintype "passive"))
      (node (ref "R13") (pin "1") (pinfunction "1_1") (pintype "passive"))
    )
    (net (code "47") (name "Net-(D25--)") (class "Default")
      (node (ref "D25") (pin "C") (pinfunction "-_C") (pintype "passive"))
      (node (ref "D26") (pin "C") (pinfunction "C_C") (pintype "passive"))
    )
    (net (code "48") (name "Net-(D26-PadA)") (class "Default")
      (node (ref "D26") (pin "A") (pinfunction "A_A") (pintype "passive"))
      (node (ref "D27") (pin "C") (pinfunction "C_C") (pintype "passive"))
      (node (ref "R14") (pin "2") (pinfunction "2_2") (pintype "passive"))
    )
    (net (code "49") (name "Net-(D29-PadC)") (class "Default")
      (node (ref "D29") (pin "C") (pinfunction "C_C") (pintype "passive"))
      (node (ref "L5") (pin "1") (pinfunction "1_1") (pintype "passive"))
      (node (ref "R17") (pin "2") (pinfunction "2_2") (pintype "passive"))
    )
    (net (code "50") (name "Net-(D30-+)") (class "Default")
      (node (ref "C9") (pin "1") (pinfunction "1_1") (pintype "passive"))
      (node (ref "D30") (pin "A") (pinfunction "+_A") (pintype "passive"))
      (node (ref "R17") (pin "1") (pinfunction "1_1") (pintype "passive"))
    )
    (net (code "51") (name "Net-(D30--)") (class "Default")
      (node (ref "D30") (pin "C") (pinfunction "-_C") (pintype "passive"))
      (node (ref "D31") (pin "C") (pinfunction "C_C") (pintype "passive"))
    )
    (net (code "52") (name "Net-(D31-PadA)") (class "Default")
      (node (ref "D31") (pin "A") (pinfunction "A_A") (pintype "passive"))
      (node (ref "D32") (pin "C") (pinfunction "C_C") (pintype "passive"))
      (node (ref "R18") (pin "2") (pinfunction "2_2") (pintype "passive"))
    )
    (net (code "53") (name "Net-(D34-PadC)") (class "Default")
      (node (ref "D34") (pin "C") (pinfunction "C_C") (pintype "passive"))
      (node (ref "L6") (pin "1") (pinfunction "1_1") (pintype "passive"))
      (node (ref "R21") (pin "2") (pinfunction "2_2") (pintype "passive"))
    )
    (net (code "54") (name "Net-(D35-+)") (class "Default")
      (node (ref "C11") (pin "1") (pinfunction "1_1") (pintype "passive"))
      (node (ref "D35") (pin "A") (pinfunction "+_A") (pintype "passive"))
      (node (ref "R21") (pin "1") (pinfunction "1_1") (pintype "passive"))
    )
    (net (code "55") (name "Net-(D35--)") (class "Default")
      (node (ref "D35") (pin "C") (pinfunction "-_C") (pintype "passive"))
      (node (ref "D36") (pin "C") (pinfunction "C_C") (pintype "passive"))
    )
    (net (code "56") (name "Net-(D36-PadA)") (class "Default")
      (node (ref "D36") (pin "A") (pinfunction "A_A") (pintype "passive"))
      (node (ref "D37") (pin "C") (pinfunction "C_C") (pintype "passive"))
      (node (ref "R22") (pin "2") (pinfunction "2_2") (pintype "passive"))
    )
    (net (code "57") (name "Net-(D39-PadC)") (class "Default")
      (node (ref "D39") (pin "C") (pinfunction "C_C") (pintype "passive"))
      (node (ref "L7") (pin "1") (pinfunction "1_1") (pintype "passive"))
      (node (ref "R25") (pin "2") (pinfunction "2_2") (pintype "passive"))
    )
    (net (code "58") (name "Net-(D40-+)") (class "Default")
      (node (ref "C13") (pin "1") (pinfunction "1_1") (pintype "passive"))
      (node (ref "D40") (pin "A") (pinfunction "+_A") (pintype "passive"))
      (node (ref "R25") (pin "1") (pinfunction "1_1") (pintype "passive"))
    )
    (net (code "59") (name "Net-(D40--)") (class "Default")
      (node (ref "D40") (pin "C") (pinfunction "-_C") (pintype "passive"))
      (node (ref "D41") (pin "C") (pinfunction "C_C") (pintype "passive"))
    )
    (net (code "60") (name "Net-(D41-PadA)") (class "Default")
      (node (ref "D41") (pin "A") (pinfunction "A_A") (pintype "passive"))
      (node (ref "D42") (pin "C") (pinfunction "C_C") (pintype "passive"))
      (node (ref "R26") (pin "2") (pinfunction "2_2") (pintype "passive"))
    )
    (net (code "61") (name "Net-(D44-PadC)") (class "Default")
      (node (ref "D44") (pin "C") (pinfunction "C_C") (pintype "passive"))
      (node (ref "L8") (pin "1") (pinfunction "1_1") (pintype "passive"))
      (node (ref "R29") (pin "2") (pinfunction "2_2") (pintype "passive"))
    )
    (net (code "62") (name "Net-(D45-+)") (class "Default")
      (node (ref "C15") (pin "1") (pinfunction "1_1") (pintype "passive"))
      (node (ref "D45") (pin "A") (pinfunction "+_A") (pintype "passive"))
      (node (ref "R29") (pin "1") (pinfunction "1_1") (pintype "passive"))
    )
    (net (code "63") (name "Net-(D45--)") (class "Default")
      (node (ref "D45") (pin "C") (pinfunction "-_C") (pintype "passive"))
      (node (ref "D46") (pin "C") (pinfunction "C_C") (pintype "passive"))
    )
    (net (code "64") (name "Net-(D46-PadA)") (class "Default")
      (node (ref "D46") (pin "A") (pinfunction "A_A") (pintype "passive"))
      (node (ref "D47") (pin "C") (pinfunction "C_C") (pintype "passive"))
      (node (ref "R30") (pin "2") (pinfunction "2_2") (pintype "passive"))
    )
    (net (code "65") (name "Net-(IC1A-I)") (class "Default")
      (node (ref "IC1") (pin "13") (pinfunction "I_13") (pintype "input"))
      (node (ref "OK1") (pin "10") (pinfunction "COL_10") (pintype "passive"))
      (node (ref "R33") (pin "2") (pinfunction "2_2") (pintype "passive"))
    )
    (net (code "66") (name "Net-(IC1A-O)") (class "Default")
      (node (ref "IC1") (pin "12") (pinfunction "O_12") (pintype "output"))
      (node (ref "IC3") (pin "2") (pinfunction "1D_2") (pintype "input"))
      (node (ref "R48") (pin "2") (pinfunction "2_2") (pintype "passive"))
    )
    (net (code "67") (name "Net-(IC1B-I)") (class "Default")
      (node (ref "IC1") (pin "11") (pinfunction "I_11") (pintype "input"))
      (node (ref "OK1") (pin "12") (pinfunction "COL_12") (pintype "passive"))
      (node (ref "R34") (pin "2") (pinfunction "2_2") (pintype "passive"))
    )
    (net (code "68") (name "Net-(IC1B-O)") (class "Default")
      (node (ref "IC1") (pin "10") (pinfunction "O_10") (pintype "output"))
      (node (ref "IC3") (pin "3") (pinfunction "2D_3") (pintype "input"))
      (node (ref "R47") (pin "2") (pinfunction "2_2") (pintype "passive"))
    )
    (net (code "69") (name "Net-(IC1C-I)") (class "Default")
      (node (ref "IC1") (pin "9") (pinfunction "I_9") (pintype "input"))
      (node (ref "OK1") (pin "14") (pinfunction "COL_14") (pintype "passive"))
      (node (ref "R35") (pin "2") (pinfunction "2_2") (pintype "passive"))
    )
    (net (code "70") (name "Net-(IC1C-O)") (class "Default")
      (node (ref "IC1") (pin "8") (pinfunction "O_8") (pintype "output"))
      (node (ref "IC3") (pin "4") (pinfunction "3D_4") (pintype "input"))
      (node (ref "R46") (pin "2") (pinfunction "2_2") (pintype "passive"))
    )
    (net (code "71") (name "Net-(IC1D-I)") (class "Default")
      (node (ref "IC1") (pin "1") (pinfunction "I_1") (pintype "input"))
      (node (ref "OK1") (pin "16") (pinfunction "COL_16") (pintype "passive"))
      (node (ref "R36") (pin "2") (pinfunction "2_2") (pintype "passive"))
    )
    (net (code "72") (name "Net-(IC1D-O)") (class "Default")
      (node (ref "IC1") (pin "2") (pinfunction "O_2") (pintype "output"))
      (node (ref "IC3") (pin "5") (pinfunction "4D_5") (pintype "input"))
      (node (ref "R45") (pin "2") (pinfunction "2_2") (pintype "passive"))
    )
    (net (code "73") (name "Net-(IC1E-I)") (class "Default")
      (node (ref "IC1") (pin "3") (pinfunction "I_3") (pintype "input"))
      (node (ref "OK2") (pin "10") (pinfunction "COL_10") (pintype "passive"))
      (node (ref "R37") (pin "2") (pinfunction "2_2") (pintype "passive"))
    )
    (net (code "74") (name "Net-(IC1E-O)") (class "Default")
      (node (ref "IC1") (pin "4") (pinfunction "O_4") (pintype "output"))
      (node (ref "IC3") (pin "6") (pinfunction "5D_6") (pintype "input"))
      (node (ref "R44") (pin "2") (pinfunction "2_2") (pintype "passive"))
    )
    (net (code "75") (name "Net-(IC1F-I)") (class "Default")
      (node (ref "IC1") (pin "5") (pinfunction "I_5") (pintype "input"))
      (node (ref "OK2") (pin "12") (pinfunction "COL_12") (pintype "passive"))
      (node (ref "R38") (pin "2") (pinfunction "2_2") (pintype "passive"))
    )
    (net (code "76") (name "Net-(IC1F-O)") (class "Default")
      (node (ref "IC1") (pin "6") (pinfunction "O_6") (pintype "output"))
      (node (ref "IC3") (pin "7") (pinfunction "6D_7") (pintype "input"))
      (node (ref "R43") (pin "2") (pinfunction "2_2") (pintype "passive"))
    )
    (net (code "77") (name "Net-(IC2A-I)") (class "Default")
      (node (ref "IC2") (pin "13") (pinfunction "I_13") (pintype "input"))
      (node (ref "OK2") (pin "16") (pinfunction "COL_16") (pintype "passive"))
      (node (ref "R40") (pin "2") (pinfunction "2_2") (pintype "passive"))
    )
    (net (code "78") (name "Net-(IC2A-O)") (class "Default")
      (node (ref "IC2") (pin "12") (pinfunction "O_12") (pintype "output"))
      (node (ref "IC3") (pin "9") (pinfunction "8D_9") (pintype "input"))
      (node (ref "R41") (pin "2") (pinfunction "2_2") (pintype "passive"))
    )
    (net (code "79") (name "Net-(IC2B-I)") (class "Default")
      (node (ref "IC2") (pin "11") (pinfunction "I_11") (pintype "input"))
      (node (ref "OK2") (pin "14") (pinfunction "COL_14") (pintype "passive"))
      (node (ref "R39") (pin "2") (pinfunction "2_2") (pintype "passive"))
    )
    (net (code "80") (name "Net-(IC2B-O)") (class "Default")
      (node (ref "IC2") (pin "10") (pinfunction "O_10") (pintype "output"))
      (node (ref "IC3") (pin "8") (pinfunction "7D_8") (pintype "input"))
      (node (ref "R42") (pin "2") (pinfunction "2_2") (pintype "passive"))
    )
    (net (code "81") (name "Net-(JP1-Pad2)") (class "Default")
      (node (ref "JP1") (pin "2") (pinfunction "2_2") (pintype "passive"))
      (node (ref "R50") (pin "1") (pinfunction "1_1") (pintype "passive"))
    )
    (net (code "82") (name "Net-(L1-Pad2)") (class "Default")
      (node (ref "L1") (pin "2") (pinfunction "2_2") (pintype "passive"))
      (node (ref "X1") (pin "2.1") (pinfunction "2_2.1") (pintype "bidirectional"))
      (node (ref "X1") (pin "2.2") (pinfunction "2_2.2") (pintype "bidirectional"))
    )
    (net (code "83") (name "Net-(L2-Pad2)") (class "Default")
      (node (ref "L2") (pin "2") (pinfunction "2_2") (pintype "passive"))
      (node (ref "X1") (pin "1.1") (pinfunction "1_1.1") (pintype "bidirectional"))
      (node (ref "X1") (pin "1.2") (pinfunction "1_1.2") (pintype "bidirectional"))
    )
    (net (code "84") (name "Net-(L3-Pad2)") (class "Default")
      (node (ref "L3") (pin "2") (pinfunction "2_2") (pintype "passive"))
      (node (ref "X2") (pin "2.1") (pinfunction "2_2.1") (pintype "bidirectional"))
      (node (ref "X2") (pin "2.2") (pinfunction "2_2.2") (pintype "bidirectional"))
    )
    (net (code "85") (name "Net-(L4-Pad2)") (class "Default")
      (node (ref "L4") (pin "2") (pinfunction "2_2") (pintype "passive"))
      (node (ref "X2") (pin "1.1") (pinfunction "1_1.1") (pintype "bidirectional"))
      (node (ref "X2") (pin "1.2") (pinfunction "1_1.2") (pintype "bidirectional"))
    )
    (net (code "86") (name "Net-(L5-Pad2)") (class "Default")
      (node (ref "L5") (pin "2") (pinfunction "2_2") (pintype "passive"))
      (node (ref "X3") (pin "2.1") (pinfunction "2_2.1") (pintype "bidirectional"))
      (node (ref "X3") (pin "2.2") (pinfunction "2_2.2") (pintype "bidirectional"))
    )
    (net (code "87") (name "Net-(L6-Pad2)") (class "Default")
      (node (ref "L6") (pin "2") (pinfunction "2_2") (pintype "passive"))
      (node (ref "X3") (pin "1.1") (pinfunction "1_1.1") (pintype "bidirectional"))
      (node (ref "X3") (pin "1.2") (pinfunction "1_1.2") (pintype "bidirectional"))
    )
    (net (code "88") (name "Net-(L7-Pad2)") (class "Default")
      (node (ref "L7") (pin "2") (pinfunction "2_2") (pintype "passive"))
      (node (ref "X4") (pin "2.1") (pinfunction "2_2.1") (pintype "bidirectional"))
      (node (ref "X4") (pin "2.2") (pinfunction "2_2.2") (pintype "bidirectional"))
    )
    (net (code "89") (name "Net-(L8-Pad2)") (class "Default")
      (node (ref "L8") (pin "2") (pinfunction "2_2") (pintype "passive"))
      (node (ref "X4") (pin "1.1") (pinfunction "1_1.1") (pintype "bidirectional"))
      (node (ref "X4") (pin "1.2") (pinfunction "1_1.2") (pintype "bidirectional"))
    )
    (net (code "90") (name "Net-(LED1-PadA)") (class "Default")
      (node (ref "LED1") (pin "A") (pinfunction "A_A") (pintype "passive"))
      (node (ref "R41") (pin "1") (pinfunction "1_1") (pintype "passive"))
    )
    (net (code "91") (name "Net-(LED2-PadA)") (class "Default")
      (node (ref "LED2") (pin "A") (pinfunction "A_A") (pintype "passive"))
      (node (ref "R42") (pin "1") (pinfunction "1_1") (pintype "passive"))
    )
    (net (code "92") (name "Net-(LED3-PadA)") (class "Default")
      (node (ref "LED3") (pin "A") (pinfunction "A_A") (pintype "passive"))
      (node (ref "R43") (pin "1") (pinfunction "1_1") (pintype "passive"))
    )
    (net (code "93") (name "Net-(LED4-PadA)") (class "Default")
      (node (ref "LED4") (pin "A") (pinfunction "A_A") (pintype "passive"))
      (node (ref "R44") (pin "1") (pinfunction "1_1") (pintype "passive"))
    )
    (net (code "94") (name "Net-(LED5-PadA)") (class "Default")
      (node (ref "LED5") (pin "A") (pinfunction "A_A") (pintype "passive"))
      (node (ref "R45") (pin "1") (pinfunction "1_1") (pintype "passive"))
    )
    (net (code "95") (name "Net-(LED6-PadA)") (class "Default")
      (node (ref "LED6") (pin "A") (pinfunction "A_A") (pintype "passive"))
      (node (ref "R46") (pin "1") (pinfunction "1_1") (pintype "passive"))
    )
    (net (code "96") (name "Net-(LED7-PadA)") (class "Default")
      (node (ref "LED7") (pin "A") (pinfunction "A_A") (pintype "passive"))
      (node (ref "R47") (pin "1") (pinfunction "1_1") (pintype "passive"))
    )
    (net (code "97") (name "Net-(LED8-PadA)") (class "Default")
      (node (ref "LED8") (pin "A") (pinfunction "A_A") (pintype "passive"))
      (node (ref "R48") (pin "1") (pinfunction "1_1") (pintype "passive"))
    )
    (net (code "98") (name "Net-(OK1A-A)") (class "Default")
      (node (ref "C8") (pin "1") (pinfunction "1_1") (pintype "passive"))
      (node (ref "OK1") (pin "1") (pinfunction "A_1") (pintype "passive"))
      (node (ref "R15") (pin "1") (pinfunction "1_1") (pintype "passive"))
      (node (ref "R16") (pin "2") (pinfunction "2_2") (pintype "passive"))
      (node (ref "U$4") (pin "2") (pinfunction "C_2") (pintype "passive"))
      (node (ref "U$4") (pin "2.1") (pinfunction "C_2.1") (pintype "passive"))
    )
    (net (code "99") (name "Net-(OK1B-A)") (class "Default")
      (node (ref "C6") (pin "1") (pinfunction "1_1") (pintype "passive"))
      (node (ref "OK1") (pin "3") (pinfunction "A_3") (pintype "passive"))
      (node (ref "R11") (pin "1") (pinfunction "1_1") (pintype "passive"))
      (node (ref "R12") (pin "2") (pinfunction "2_2") (pintype "passive"))
      (node (ref "U$3") (pin "2") (pinfunction "C_2") (pintype "passive"))
      (node (ref "U$3") (pin "2.1") (pinfunction "C_2.1") (pintype "passive"))
    )
    (net (code "100") (name "Net-(OK1C-A)") (class "Default")
      (node (ref "C4") (pin "1") (pinfunction "1_1") (pintype "passive"))
      (node (ref "OK1") (pin "5") (pinfunction "A_5") (pintype "passive"))
      (node (ref "R7") (pin "1") (pinfunction "1_1") (pintype "passive"))
      (node (ref "R8") (pin "2") (pinfunction "2_2") (pintype "passive"))
      (node (ref "U$2") (pin "2") (pinfunction "C_2") (pintype "passive"))
      (node (ref "U$2") (pin "2.1") (pinfunction "C_2.1") (pintype "passive"))
    )
    (net (code "101") (name "Net-(OK1D-A)") (class "Default")
      (node (ref "C2") (pin "1") (pinfunction "1_1") (pintype "passive"))
      (node (ref "OK1") (pin "7") (pinfunction "A_7") (pintype "passive"))
      (node (ref "R3") (pin "1") (pinfunction "1_1") (pintype "passive"))
      (node (ref "R4") (pin "2") (pinfunction "2_2") (pintype "passive"))
      (node (ref "U$1") (pin "2") (pinfunction "C_2") (pintype "passive"))
      (node (ref "U$1") (pin "2.1") (pinfunction "C_2.1") (pintype "passive"))
    )
    (net (code "102") (name "Net-(OK2A-A)") (class "Default")
      (node (ref "C16") (pin "1") (pinfunction "1_1") (pintype "passive"))
      (node (ref "OK2") (pin "1") (pinfunction "A_1") (pintype "passive"))
      (node (ref "R31") (pin "1") (pinfunction "1_1") (pintype "passive"))
      (node (ref "R32") (pin "2") (pinfunction "2_2") (pintype "passive"))
      (node (ref "U$8") (pin "2") (pinfunction "C_2") (pintype "passive"))
      (node (ref "U$8") (pin "2.1") (pinfunction "C_2.1") (pintype "passive"))
    )
    (net (code "103") (name "Net-(OK2B-A)") (class "Default")
      (node (ref "C14") (pin "1") (pinfunction "1_1") (pintype "passive"))
      (node (ref "OK2") (pin "3") (pinfunction "A_3") (pintype "passive"))
      (node (ref "R27") (pin "1") (pinfunction "1_1") (pintype "passive"))
      (node (ref "R28") (pin "2") (pinfunction "2_2") (pintype "passive"))
      (node (ref "U$7") (pin "2") (pinfunction "C_2") (pintype "passive"))
      (node (ref "U$7") (pin "2.1") (pinfunction "C_2.1") (pintype "passive"))
    )
    (net (code "104") (name "Net-(OK2C-A)") (class "Default")
      (node (ref "C12") (pin "1") (pinfunction "1_1") (pintype "passive"))
      (node (ref "OK2") (pin "5") (pinfunction "A_5") (pintype "passive"))
      (node (ref "R23") (pin "1") (pinfunction "1_1") (pintype "passive"))
      (node (ref "R24") (pin "2") (pinfunction "2_2") (pintype "passive"))
      (node (ref "U$6") (pin "2") (pinfunction "C_2") (pintype "passive"))
      (node (ref "U$6") (pin "2.1") (pinfunction "C_2.1") (pintype "passive"))
    )
    (net (code "105") (name "Net-(OK2D-A)") (class "Default")
      (node (ref "C10") (pin "1") (pinfunction "1_1") (pintype "passive"))
      (node (ref "OK2") (pin "7") (pinfunction "A_7") (pintype "passive"))
      (node (ref "R19") (pin "1") (pinfunction "1_1") (pintype "passive"))
      (node (ref "R20") (pin "2") (pinfunction "2_2") (pintype "passive"))
      (node (ref "U$5") (pin "2") (pinfunction "C_2") (pintype "passive"))
      (node (ref "U$5") (pin "2.1") (pinfunction "C_2.1") (pintype "passive"))
    )
    (net (code "106") (name "Net-(Q2-OUT)") (class "Default")
      (node (ref "Q2") (pin "3") (pinfunction "OUT_3") (pintype "output"))
      (node (ref "U1") (pin "7") (pinfunction "PB6(XTAL1/TOSC1)_7") (pintype "bidirectional"))
    )
    (net (code "107") (name "Net-(U$1-B)") (class "Default")
      (node (ref "D4") (pin "A") (pinfunction "A_A") (pintype "passive"))
      (node (ref "R3") (pin "2") (pinfunction "2_2") (pintype "passive"))
      (node (ref "U$1") (pin "1") (pinfunction "B_1") (pintype "passive"))
    )
    (net (code "108") (name "Net-(U$1-E)") (class "Default")
      (node (ref "R2") (pin "1") (pinfunction "1_1") (pintype "passive"))
      (node (ref "U$1") (pin "3") (pinfunction "E_3") (pintype "passive"))
    )
    (net (code "109") (name "Net-(U$2-B)") (class "Default")
      (node (ref "D9") (pin "A") (pinfunction "A_A") (pintype "passive"))
      (node (ref "R7") (pin "2") (pinfunction "2_2") (pintype "passive"))
      (node (ref "U$2") (pin "1") (pinfunction "B_1") (pintype "passive"))
    )
    (net (code "110") (name "Net-(U$2-E)") (class "Default")
      (node (ref "R6") (pin "1") (pinfunction "1_1") (pintype "passive"))
      (node (ref "U$2") (pin "3") (pinfunction "E_3") (pintype "passive"))
    )
    (net (code "111") (name "Net-(U$3-B)") (class "Default")
      (node (ref "D22") (pin "A") (pinfunction "A_A") (pintype "passive"))
      (node (ref "R11") (pin "2") (pinfunction "2_2") (pintype "passive"))
      (node (ref "U$3") (pin "1") (pinfunction "B_1") (pintype "passive"))
    )
    (net (code "112") (name "Net-(U$3-E)") (class "Default")
      (node (ref "R10") (pin "1") (pinfunction "1_1") (pintype "passive"))
      (node (ref "U$3") (pin "3") (pinfunction "E_3") (pintype "passive"))
    )
    (net (code "113") (name "Net-(U$4-B)") (class "Default")
      (node (ref "D27") (pin "A") (pinfunction "A_A") (pintype "passive"))
      (node (ref "R15") (pin "2") (pinfunction "2_2") (pintype "passive"))
      (node (ref "U$4") (pin "1") (pinfunction "B_1") (pintype "passive"))
    )
    (net (code "114") (name "Net-(U$4-E)") (class "Default")
      (node (ref "R14") (pin "1") (pinfunction "1_1") (pintype "passive"))
      (node (ref "U$4") (pin "3") (pinfunction "E_3") (pintype "passive"))
    )
    (net (code "115") (name "Net-(U$5-B)") (class "Default")
      (node (ref "D32") (pin "A") (pinfunction "A_A") (pintype "passive"))
      (node (ref "R19") (pin "2") (pinfunction "2_2") (pintype "passive"))
      (node (ref "U$5") (pin "1") (pinfunction "B_1") (pintype "passive"))
    )
    (net (code "116") (name "Net-(U$5-E)") (class "Default")
      (node (ref "R18") (pin "1") (pinfunction "1_1") (pintype "passive"))
      (node (ref "U$5") (pin "3") (pinfunction "E_3") (pintype "passive"))
    )
    (net (code "117") (name "Net-(U$6-B)") (class "Default")
      (node (ref "D37") (pin "A") (pinfunction "A_A") (pintype "passive"))
      (node (ref "R23") (pin "2") (pinfunction "2_2") (pintype "passive"))
      (node (ref "U$6") (pin "1") (pinfunction "B_1") (pintype "passive"))
    )
    (net (code "118") (name "Net-(U$6-E)") (class "Default")
      (node (ref "R22") (pin "1") (pinfunction "1_1") (pintype "passive"))
      (node (ref "U$6") (pin "3") (pinfunction "E_3") (pintype "passive"))
    )
    (net (code "119") (name "Net-(U$7-B)") (class "Default")
      (node (ref "D42") (pin "A") (pinfunction "A_A") (pintype "passive"))
      (node (ref "R27") (pin "2") (pinfunction "2_2") (pintype "passive"))
      (node (ref "U$7") (pin "1") (pinfunction "B_1") (pintype "passive"))
    )
    (net (code "120") (name "Net-(U$7-E)") (class "Default")
      (node (ref "R26") (pin "1") (pinfunction "1_1") (pintype "passive"))
      (node (ref "U$7") (pin "3") (pinfunction "E_3") (pintype "passive"))
    )
    (net (code "121") (name "Net-(U$8-B)") (class "Default")
      (node (ref "D47") (pin "A") (pinfunction "A_A") (pintype "passive"))
      (node (ref "R31") (pin "2") (pinfunction "2_2") (pintype "passive"))
      (node (ref "U$8") (pin "1") (pinfunction "B_1") (pintype "passive"))
    )
    (net (code "122") (name "Net-(U$8-E)") (class "Default")
      (node (ref "R30") (pin "1") (pinfunction "1_1") (pintype "passive"))
      (node (ref "U$8") (pin "3") (pinfunction "E_3") (pintype "passive"))
    )
    (net (code "123") (name "unconnected-(IC2C-O-Pad8)") (class "Default")
      (node (ref "IC2") (pin "8") (pinfunction "O_8") (pintype "output"))
    )
    (net (code "124") (name "unconnected-(IC2D-O-Pad2)") (class "Default")
      (node (ref "IC2") (pin "2") (pinfunction "O_2") (pintype "output"))
    )
    (net (code "125") (name "unconnected-(IC2E-O-Pad4)") (class "Default")
      (node (ref "IC2") (pin "4") (pinfunction "O_4") (pintype "output"))
    )
    (net (code "126") (name "unconnected-(IC2F-O-Pad6)") (class "Default")
      (node (ref "IC2") (pin "6") (pinfunction "O_6") (pintype "output"))
    )
    (net (code "127") (name "unconnected-(Q2-TS-Pad1)") (class "Default")
      (node (ref "Q2") (pin "1") (pinfunction "TS_1") (pintype "passive"))
    )
    (net (code "128") (name "unconnected-(U1-PB0(ICP)-Pad12)") (class "Default")
      (node (ref "U1") (pin "12") (pinfunction "PB0(ICP)_12") (pintype "bidirectional"))
    )
    (net (code "129") (name "unconnected-(U1-PB1(OC1A)-Pad13)") (class "Default")
      (node (ref "U1") (pin "13") (pinfunction "PB1(OC1A)_13") (pintype "bidirectional"))
    )
    (net (code "130") (name "unconnected-(U1-PB2(SS{slash}OC1B)-Pad14)") (class "Default")
      (node (ref "U1") (pin "14") (pinfunction "PB2(SS/OC1B)_14") (pintype "bidirectional"))
    )
    (net (code "131") (name "unconnected-(U1-PB7(XTAL2{slash}TOSC2)-Pad8)") (class "Default")
      (node (ref "U1") (pin "8") (pinfunction "PB7(XTAL2/TOSC2)_8") (pintype "bidirectional"))
    )
    (net (code "132") (name "unconnected-(U1-PD5(T1)-Pad9)") (class "Default")
      (node (ref "U1") (pin "9") (pinfunction "PD5(T1)_9") (pintype "bidirectional"))
    )
    (net (code "133") (name "unconnected-(U1-PD6(AIN0)-Pad10)") (class "Default")
      (node (ref "U1") (pin "10") (pinfunction "PD6(AIN0)_10") (pintype "bidirectional"))
    )
  )
)
